# electrosteel2020_block.net
KiCad netlist of a schematic drawn in EAGLE
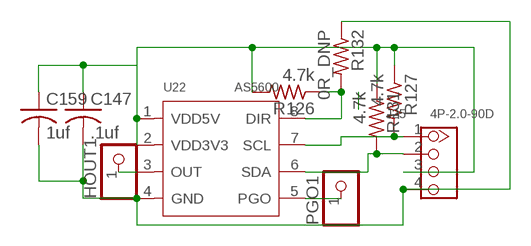
[diagram p0: schematic, sheet 1]

(export (version "E")
  (design (tool "Eeschema 10.0.6"))
  (components
    (comp (ref "C147")
      (value ".1uf")
      (footprint "eagle-import:C0603K")
      (fields (field (name "PARTNO") "CC0603KRX7R8BB104"))
      (libsource (lib "eagle-import") (part "C-USC0603K"))
    )
    (comp (ref "C159")
      (value "1uf")
      (footprint "eagle-import:C1206K")
      (fields (field (name "PARTNO") "C3216X7R1E105K085AA"))
      (libsource (lib "eagle-import") (part "C-USC1206K"))
    )
    (comp (ref "HOUT1")
      (value "PINHD-1X1")
      (footprint "eagle-import:1X01")
      (fields (field (name "PARTNO") "*DNP"))
      (libsource (lib "eagle-import") (part "PINHD-1X1"))
    )
    (comp (ref "J25")
      (value "4P-2.0-90D")
      (footprint "eagle-import:HW4-2.0-90D")
      (libsource (lib "eagle-import") (part "GROVE-CONNECTOR-DIP-90D(4P-2.0)"))
    )
    (comp (ref "PGO1")
      (value "PINHD-1X1")
      (footprint "eagle-import:1X01")
      (fields (field (name "PARTNO") "*DNP"))
      (libsource (lib "eagle-import") (part "PINHD-1X1"))
    )
    (comp (ref "R126")
      (value "4.7k")
      (footprint "eagle-import:R0603")
      (fields (field (name "PARTNO") "ESR03EZPJ470"))
      (libsource (lib "eagle-import") (part "R-US_R0603"))
    )
    (comp (ref "R127")
      (value "4.7k")
      (footprint "eagle-import:R0603")
      (fields (field (name "PARTNO") "ESR03EZPJ470"))
      (libsource (lib "eagle-import") (part "R-US_R0603"))
    )
    (comp (ref "R131")
      (value "4.7k")
      (footprint "eagle-import:R0603")
      (fields (field (name "PARTNO") "ESR03EZPJ470"))
      (libsource (lib "eagle-import") (part "R-US_R0603"))
    )
    (comp (ref "R132")
      (value "0R_DNP")
      (footprint "eagle-import:R0603")
      (fields (field (name "PARTNO") "ESR03EZPJ470"))
      (libsource (lib "eagle-import") (part "R-US_R0603"))
    )
    (comp (ref "U22")
      (value "AS5600")
      (footprint "eagle-import:SOIC8-1.27-5X4MM")
      (libsource (lib "eagle-import") (part "SENSOR-AS5600"))
    )
  )
  (nets
    (net (code "1") (name "Net-(U22-DIR)") (class "Default")
      (node (ref "R126") (pin "1") (pinfunction "1_1") (pintype "passive"))
      (node (ref "R132") (pin "2") (pinfunction "2_2") (pintype "passive"))
      (node (ref "U22") (pin "8") (pinfunction "DIR_8") (pintype "bidirectional"))
    )
    (net (code "2") (name "Net-(U22-GND)") (class "Default")
      (node (ref "C147") (pin "2") (pinfunction "2_2") (pintype "passive"))
      (node (ref "C159") (pin "2") (pinfunction "2_2") (pintype "passive"))
      (node (ref "J25") (pin "4") (pinfunction "4_4") (pintype "bidirectional"))
      (node (ref "R132") (pin "1") (pinfunction "1_1") (pintype "passive"))
      (node (ref "U22") (pin "4") (pinfunction "GND_4") (pintype "bidirectional"))
    )
    (net (code "3") (name "Net-(U22-OUT)") (class "Default")
      (node (ref "HOUT1") (pin "1") (pinfunction "1_1") (pintype "passive"))
      (node (ref "U22") (pin "3") (pinfunction "OUT_3") (pintype "bidirectional"))
    )
    (net (code "4") (name "Net-(U22-PGO)") (class "Default")
      (node (ref "PGO1") (pin "1") (pinfunction "1_1") (pintype "passive"))
      (node (ref "U22") (pin "5") (pinfunction "PGO_5") (pintype "bidirectional"))
    )
    (net (code "5") (name "Net-(U22-SCL)") (class "Default")
      (node (ref "J25") (pin "1") (pinfunction "1_1") (pintype "bidirectional"))
      (node (ref "R127") (pin "2") (pinfunction "2_2") (pintype "passive"))
      (node (ref "U22") (pin "7") (pinfunction "SCL_7") (pintype "bidirectional"))
    )
    (net (code "6") (name "Net-(U22-SDA)") (class "Default")
      (node (ref "J25") (pin "2") (pinfunction "2_2") (pintype "bidirectional"))
      (node (ref "R131") (pin "2") (pinfunction "2_2") (pintype "passive"))
      (node (ref "U22") (pin "6") (pinfunction "SDA_6") (pintype "bidirectional"))
    )
    (net (code "7") (name "Net-(U22-VDD3V3)") (class "Default")
      (node (ref "C147") (pin "1") (pinfunction "1_1") (pintype "passive"))
      (node (ref "C159") (pin "1") (pinfunction "1_1") (pintype "passive"))
      (node (ref "J25") (pin "3") (pinfunction "3_3") (pintype "bidirectional"))
      (node (ref "R126") (pin "2") (pinfunction "2_2") (pintype "passive"))
      (node (ref "R127") (pin "1") (pinfunction "1_1") (pintype "passive"))
      (node (ref "R131") (pin "1") (pinfunction "1_1") (pintype "passive"))
      (node (ref "U22") (pin "1") (pinfunction "VDD5V_1") (pintype "bidirectional"))
      (node (ref "U22") (pin "2") (pinfunction "VDD3V3_2") (pintype "bidirectional"))
    )
  )
)
